# power.net
KiCad netlist of a schematic drawn in Altium Designer
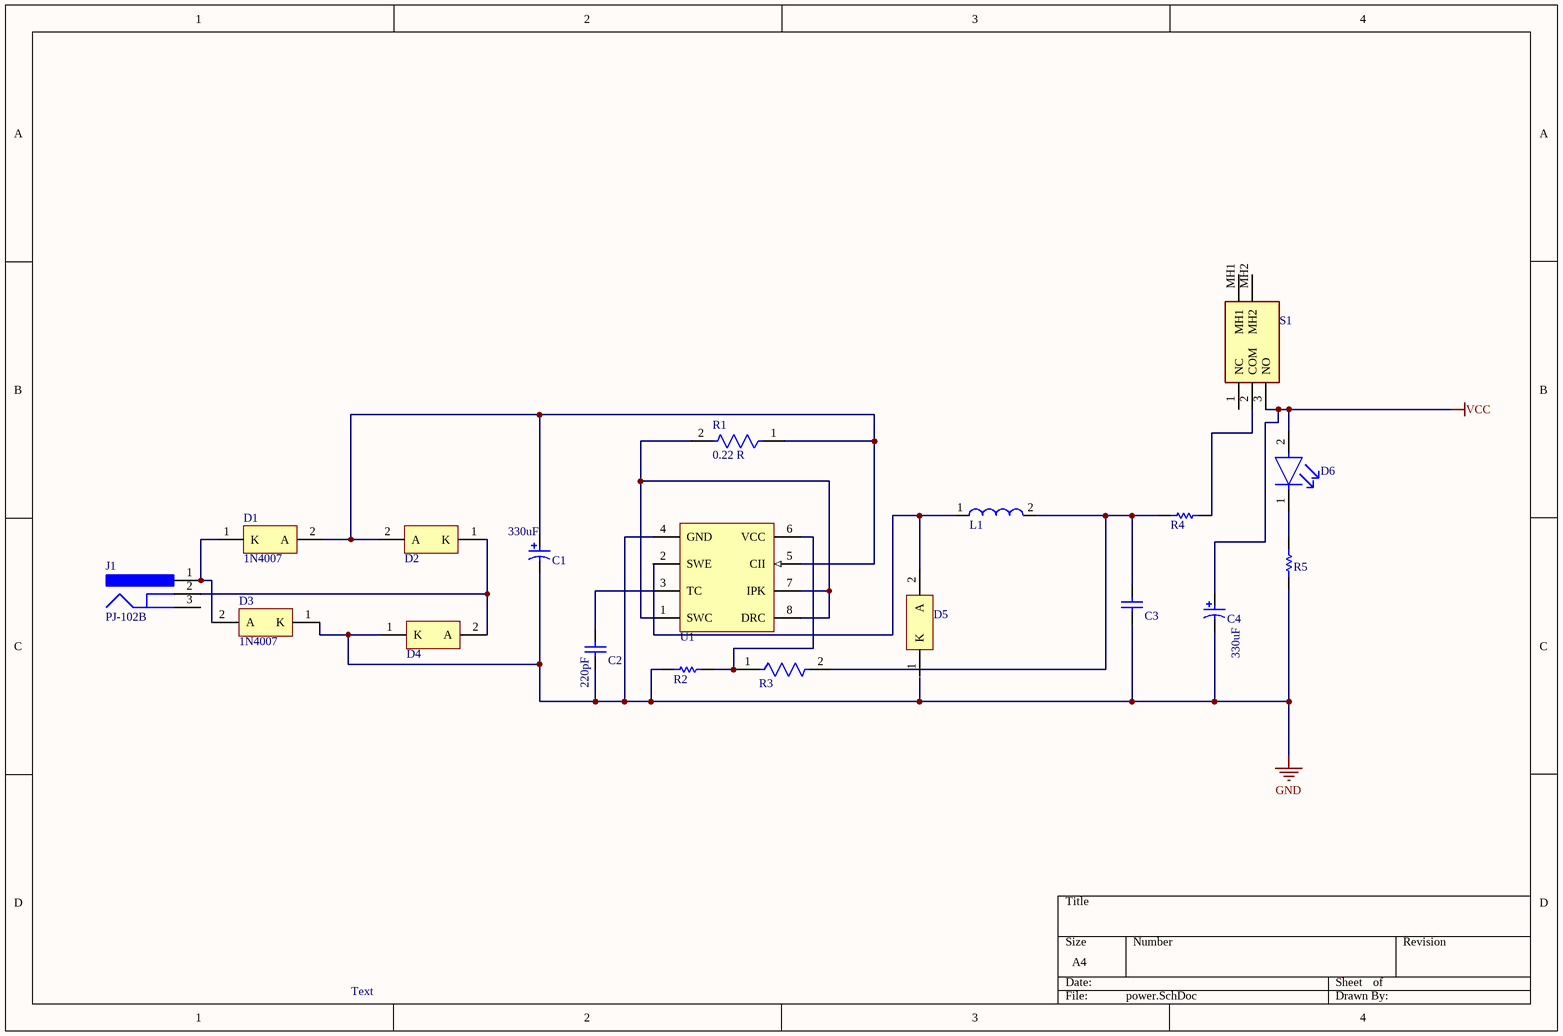
[diagram p0: power.SchDoc]

(export (version "E")
  (design (tool "Eeschema 10.0.6"))
  (components
    (comp (ref "C1")
      (value "EEE-FK1V331P")
      (footprint "PNSC-EEE-FK1V331P_L")
      (description "Aluminum Electrolytic Capacitor, 330 uF, 35 V, -55 to 105 degC, 2-Pin CAPAE, RoHS, Tape and Reel")
      (fields (field (name "MANUFACTURER") "Panasonic"))
      (libsource (lib "Altium Content Vault") (part "CAP-P-2"))
    )
    (comp (ref "C2")
      (value "VJ0603D201KXAAJ")
      (footprint "CAPC1608X92X38LL15T08")
      (fields (field (name "MANUFACTURER") "Vitramon"))
      (libsource (lib "Altium Content Vault") (part "CAP"))
    )
    (comp (ref "C3")
      (value "GRM188R60J106ME47D")
      (footprint "CAPC1608X90X35NL10T15")
      (fields (field (name "MANUFACTURER") "Murata"))
      (libsource (lib "Altium Content Vault") (part "CAP"))
    )
    (comp (ref "C4")
      (value "EEE-FK1V331P")
      (footprint "PNSC-EEE-FK1V331P_L")
      (description "Aluminum Electrolytic Capacitor, 330 uF, 35 V, -55 to 105 degC, 2-Pin CAPAE, RoHS, Tape and Reel")
      (fields (field (name "MANUFACTURER") "Panasonic"))
      (libsource (lib "Altium Content Vault") (part "CAP-P-2"))
    )
    (comp (ref "D1")
      (value "1N4007")
      (footprint "ONSC-AXIAL_LEAD-2-59-10_P")
      (description "Standard Recovery Rectifier, 2-Pin Axial_Lead, Pb-Free, Bulk Bag")
      (fields (field (name "MANUFACTURER") "On Semiconductor"))
      (libsource (lib "") (part "ONSC-D-K1A2-2_A_2"))
    )
    (comp (ref "D2")
      (value "1N4007")
      (footprint "ONSC-AXIAL_LEAD-2-59-10_P")
      (description "Standard Recovery Rectifier, 2-Pin Axial_Lead, Pb-Free, Bulk Bag")
      (fields (field (name "MANUFACTURER") "On Semiconductor"))
      (libsource (lib "Altium Content Vault") (part "ONSC-D-K1A2-2_A"))
    )
    (comp (ref "D3")
      (value "1N4007")
      (footprint "ONSC-AXIAL_LEAD-2-59-10_P")
      (description "Standard Recovery Rectifier, 2-Pin Axial_Lead, Pb-Free, Bulk Bag")
      (fields (field (name "MANUFACTURER") "On Semiconductor"))
      (libsource (lib "Altium Content Vault") (part "ONSC-D-K1A2-2_A"))
    )
    (comp (ref "D4")
      (value "1N4007")
      (footprint "ONSC-AXIAL_LEAD-2-59-10_P")
      (description "Standard Recovery Rectifier, 2-Pin Axial_Lead, Pb-Free, Bulk Bag")
      (fields (field (name "MANUFACTURER") "On Semiconductor"))
      (libsource (lib "") (part "ONSC-D-K1A2-2_A_2"))
    )
    (comp (ref "D5")
      (value "MBRS140T3G")
      (footprint "ONSC-SMB-2-403A-03_H_V")
      (description "Schottky Power Rectifier, 2-Pin SMB, Pb-Free, Tape and Reel")
      (fields (field (name "MANUFACTURER") "On Semiconductor"))
      (libsource (lib "") (part "ONSC-D-K1A2-2_A_1"))
    )
    (comp (ref "D6")
      (value "LTST-C190GKT")
      (footprint "FP-LTST-C190GKT-MFG")
      (description "LED GREEN CLEAR CHIP SMD")
      (fields (field (name "VOLTAGE") "2V"))
      (libsource (lib "Altium Content Vault") (part "8706943c75ba83719d021d2fdc84c58"))
    )
    (comp (ref "J1")
      (value "PJ-102B")
      (footprint "CUI-PJ-102B_V")
      (fields (field (name "MANUFACTURER") "CUIInc."))
      (libsource (lib "Altium Content Vault") (part "JACK-2CD3-RN"))
    )
    (comp (ref "L1")
      (value "744774222")
      (footprint "WE-PD2-M")
      (description "SMD Power Inductor WE-PD2, L = 220 µH")
      (libsource (lib "Altium Content Vault") (part "PAS-IND-INDUCTOR-2"))
    )
    (comp (ref "R1")
      (value "CRCW04022K70FKED")
      (footprint "FP-CRCW0402-e3-IPC_C")
      (description "RES Thick Film, 0.22 Ω, 1%, 0.063W, 100ppm/°C, 0402")
      (fields (field (name "TOLERANCE") "1%") (field (name "RESISTANCE") "0.22 R"))
      (libsource (lib "Altium Content Vault") (part "1029c3af85768c4190bb7ad29bc67b5"))
    )
    (comp (ref "R2")
      (value "CRCW08051K00FKEA")
      (footprint "RESC2013X50X30NL20T20")
      (fields (field (name "MANUFACTURER") "Vishay Dale"))
      (libsource (lib "Altium Content Vault") (part "RES"))
    )
    (comp (ref "R3")
      (value "CRCW06033K00FKEA")
      (footprint "FP-CRCW0603-e3-MFG")
      (description "RES Thick Film, 3kΩ, 1%, 0.1W, 100ppm/°C, 0603")
      (fields (field (name "TOLERANCE") "1%"))
      (libsource (lib "Altium Content Vault") (part "1029c3af85768c4190bb7ad29bc67b5"))
    )
    (comp (ref "R4")
      (value "Jumper 2512(6432)")
      (footprint "RESC2512(6432)_L")
      (description "Jumper 2512 (6432 Metric)")
      (fields (field (name "TOLERANCE") "None"))
      (libsource (lib "Altium Content Vault") (part "RES"))
    )
    (comp (ref "R5")
      (value "RC0402FR-072K2L")
      (footprint "RESC1005X40X25NL05T10")
      (fields (field (name "MANUFACTURER") "Yageo / Phycomp"))
      (libsource (lib "Altium Content Vault") (part "RES"))
    )
    (comp (ref "S1")
      (value "MS12ASW40")
      (footprint "SamacSys:MS12ASW40")
      (description "Switch")
      (fields (field (name "MOUSER PART NUMBER") "633-MS12ASW40"))
      (libsource (lib "SamacSys") (part "MS12ASW40"))
    )
    (comp (ref "U1")
      (value "MC34063ACD-TR")
      (footprint "SO8_M")
      (description "DC/DC converter control circuit, 8-Pin SO, Tape and Reel")
      (libsource (lib "Altium Content Vault") (part "PM-SWREG-MC34063-IL8"))
    )
  )
  (nets
    (net (code "1") (name "GND") (class "Default")
      (node (ref "C1") (pin "2") (pinfunction "2_2") (pintype "passive"))
      (node (ref "C2") (pin "1") (pinfunction "1_1") (pintype "passive"))
      (node (ref "C3") (pin "1") (pinfunction "1_1") (pintype "passive"))
      (node (ref "C4") (pin "2") (pinfunction "2_2") (pintype "passive"))
      (node (ref "D3") (pin "1") (pinfunction "K_1") (pintype "passive"))
      (node (ref "D4") (pin "1") (pinfunction "K_1") (pintype "passive"))
      (node (ref "R2") (pin "1") (pinfunction "1_1") (pintype "passive"))
      (node (ref "R5") (pin "2") (pinfunction "2_2") (pintype "passive"))
      (node (ref "U1") (pin "4") (pinfunction "GND_4") (pintype "power_in"))
    )
    (net (code "2") (name "Net-(C3-Pad2)") (class "Default")
      (node (ref "C3") (pin "2") (pinfunction "2_2") (pintype "passive"))
      (node (ref "L1") (pin "2") (pinfunction "2_2") (pintype "passive"))
      (node (ref "R3") (pin "2") (pinfunction "2_2") (pintype "passive"))
      (node (ref "R4") (pin "1") (pinfunction "1_1") (pintype "passive"))
    )
    (net (code "3") (name "Net-(D1-A)") (class "Default")
      (node (ref "C1") (pin "1") (pinfunction "1_1") (pintype "passive"))
      (node (ref "D1") (pin "2") (pinfunction "A_2") (pintype "passive"))
      (node (ref "D2") (pin "2") (pinfunction "A_2") (pintype "passive"))
      (node (ref "R1") (pin "1") (pinfunction "1_1") (pintype "passive"))
      (node (ref "U1") (pin "5") (pinfunction "CII_5") (pintype "input"))
    )
    (net (code "4") (name "Net-(D1-K)") (class "Default")
      (node (ref "D1") (pin "1") (pinfunction "K_1") (pintype "passive"))
      (node (ref "D3") (pin "2") (pinfunction "A_2") (pintype "passive"))
      (node (ref "J1") (pin "1") (pinfunction "1_1") (pintype "passive"))
    )
    (net (code "5") (name "Net-(D2-K)") (class "Default")
      (node (ref "D2") (pin "1") (pinfunction "K_1") (pintype "passive"))
      (node (ref "D4") (pin "2") (pinfunction "A_2") (pintype "passive"))
      (node (ref "J1") (pin "2") (pinfunction "2_2") (pintype "passive"))
    )
    (net (code "6") (name "Net-(D5-A)") (class "Default")
      (node (ref "D5") (pin "2") (pinfunction "A_2") (pintype "passive"))
      (node (ref "L1") (pin "1") (pinfunction "1_1") (pintype "passive"))
      (node (ref "U1") (pin "2") (pinfunction "SWE_2") (pintype "open_emitter"))
    )
    (net (code "7") (name "Net-(D6-C)") (class "Default")
      (node (ref "D6") (pin "1") (pinfunction "C_1") (pintype "passive"))
      (node (ref "R5") (pin "1") (pinfunction "1_1") (pintype "passive"))
    )
    (net (code "8") (name "Net-(S1-COM)") (class "Default")
      (node (ref "R4") (pin "2") (pinfunction "2_2") (pintype "passive"))
      (node (ref "S1") (pin "2") (pinfunction "COM_2") (pintype "passive"))
    )
    (net (code "9") (name "Net-(U1-DRC)") (class "Default")
      (node (ref "R1") (pin "2") (pinfunction "2_2") (pintype "passive"))
      (node (ref "U1") (pin "1") (pinfunction "SWC_1") (pintype "open_collector"))
      (node (ref "U1") (pin "7") (pinfunction "IPK_7") (pintype "passive"))
      (node (ref "U1") (pin "8") (pinfunction "DRC_8") (pintype "open_collector"))
    )
    (net (code "10") (name "Net-(U1-TC)") (class "Default")
      (node (ref "C2") (pin "2") (pinfunction "2_2") (pintype "passive"))
      (node (ref "U1") (pin "3") (pinfunction "TC_3") (pintype "passive"))
    )
    (net (code "11") (name "Net-(U1-VCC)") (class "Default")
      (node (ref "R2") (pin "2") (pinfunction "2_2") (pintype "passive"))
      (node (ref "R3") (pin "1") (pinfunction "1_1") (pintype "passive"))
      (node (ref "U1") (pin "6") (pinfunction "VCC_6") (pintype "power_in"))
    )
    (net (code "12") (name "VCC") (class "Default")
      (node (ref "C4") (pin "1") (pinfunction "1_1") (pintype "passive"))
      (node (ref "D6") (pin "2") (pinfunction "A_2") (pintype "passive"))
      (node (ref "S1") (pin "3") (pinfunction "NO_3") (pintype "passive"))
    )
    (net (code "13") (name "unconnected-(D5-K-Pad1)") (class "Default")
      (node (ref "D5") (pin "1") (pinfunction "K_1") (pintype "passive"))
    )
    (net (code "14") (name "unconnected-(J1-Pad3)") (class "Default")
      (node (ref "J1") (pin "3") (pinfunction "3_3") (pintype "passive"))
    )
    (net (code "15") (name "unconnected-(S1-NC-Pad1)") (class "Default")
      (node (ref "S1") (pin "1") (pinfunction "NC_1") (pintype "passive"))
    )
    (net (code "16") (name "unconnected-(S1-PadMH1)") (class "Default")
      (node (ref "S1") (pin "MH1") (pinfunction "MH1_MH1") (pintype "passive"))
    )
    (net (code "17") (name "unconnected-(S1-PadMH2)") (class "Default")
      (node (ref "S1") (pin "MH2") (pinfunction "MH2_MH2") (pintype "passive"))
    )
  )
)
